# Sheet1.net
KiCad netlist of a schematic drawn in Altium Designer
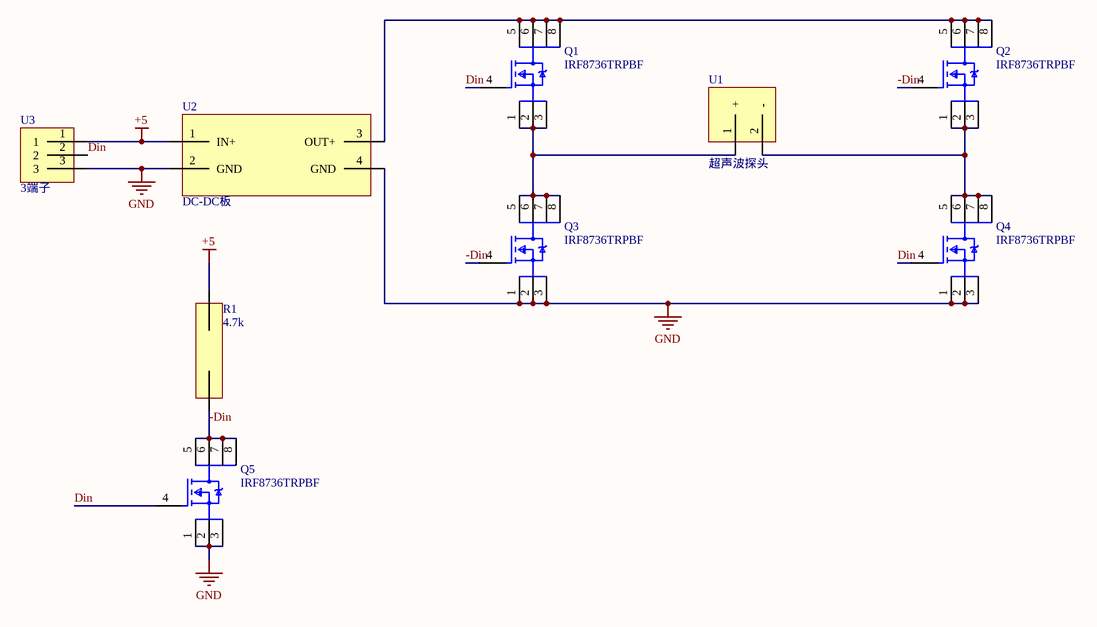
[diagram p0: Sheet1.SchDoc]

(export (version "E")
  (design (tool "Eeschema 10.0.6"))
  (components
    (comp (ref "Q1")
      (value "IRF8736TRPBF")
      (footprint "FP-PG-DSO-8-MFG")
      (description "MOSFET N-CH 30V 18A 8-SOIC")
      (fields
        (field (name "MANUFACTURER") "Infineon")
        (field (name "OCTOPART") "https://octopart.com/irf8736trpbf-infineon-65873731")
      )
      (libsource (lib "Altium Content Vault") (part "6c4379695d6b9ddabb25581bf066c8b"))
    )
    (comp (ref "Q2")
      (value "IRF8736TRPBF")
      (footprint "FP-PG-DSO-8-MFG")
      (description "MOSFET N-CH 30V 18A 8-SOIC")
      (fields
        (field (name "MANUFACTURER") "Infineon")
        (field (name "OCTOPART") "https://octopart.com/irf8736trpbf-infineon-65873731")
      )
      (libsource (lib "Altium Content Vault") (part "6c4379695d6b9ddabb25581bf066c8b"))
    )
    (comp (ref "Q3")
      (value "IRF8736TRPBF")
      (footprint "FP-PG-DSO-8-MFG")
      (description "MOSFET N-CH 30V 18A 8-SOIC")
      (fields
        (field (name "MANUFACTURER") "Infineon")
        (field (name "OCTOPART") "https://octopart.com/irf8736trpbf-infineon-65873731")
      )
      (libsource (lib "Altium Content Vault") (part "6c4379695d6b9ddabb25581bf066c8b"))
    )
    (comp (ref "Q4")
      (value "IRF8736TRPBF")
      (footprint "FP-PG-DSO-8-MFG")
      (description "MOSFET N-CH 30V 18A 8-SOIC")
      (fields
        (field (name "MANUFACTURER") "Infineon")
        (field (name "OCTOPART") "https://octopart.com/irf8736trpbf-infineon-65873731")
      )
      (libsource (lib "Altium Content Vault") (part "6c4379695d6b9ddabb25581bf066c8b"))
    )
    (comp (ref "Q5")
      (value "IRF8736TRPBF")
      (footprint "FP-PG-DSO-8-MFG")
      (description "MOSFET N-CH 30V 18A 8-SOIC")
      (fields
        (field (name "MANUFACTURER") "Infineon")
        (field (name "OCTOPART") "https://octopart.com/irf8736trpbf-infineon-65873731")
      )
      (libsource (lib "Altium Content Vault") (part "6c4379695d6b9ddabb25581bf066c8b"))
    )
    (comp (ref "R1") (value "4.7k") (footprint "0603") (libsource (lib "Schlib1") (part "0603")))
    (comp (ref "U1") (value "超声波探头") (footprint "超声波探头") (libsource (lib "Schlib1") (part "超声波探头")))
    (comp (ref "U2") (value "DC-DC板") (footprint "DC-DC板") (libsource (lib "Schlib1") (part "DC-DC板")))
    (comp (ref "U3") (value "3端子") (footprint "HDR2.54-LI-3P") (libsource (lib "Schlib1") (part "3端子")))
  )
  (nets
    (net (code "1") (name "+5") (class "Default")
      (node (ref "R1") (pin "2") (pinfunction "2_2") (pintype "passive"))
      (node (ref "U2") (pin "1") (pinfunction "IN+_1") (pintype "passive"))
      (node (ref "U3") (pin "1") (pinfunction "1_1") (pintype "passive"))
    )
    (net (code "2") (name "/-Din") (class "Default")
      (node (ref "Q2") (pin "4") (pinfunction "G_4") (pintype "passive"))
      (node (ref "Q3") (pin "4") (pinfunction "G_4") (pintype "passive"))
      (node (ref "Q5") (pin "5") (pinfunction "D_5") (pintype "passive"))
      (node (ref "Q5") (pin "6") (pinfunction "D_6") (pintype "passive"))
      (node (ref "Q5") (pin "7") (pinfunction "D_7") (pintype "passive"))
      (node (ref "Q5") (pin "8") (pinfunction "D_8") (pintype "passive"))
      (node (ref "R1") (pin "1") (pinfunction "1_1") (pintype "passive"))
    )
    (net (code "3") (name "/Din") (class "Default")
      (node (ref "Q1") (pin "4") (pinfunction "G_4") (pintype "passive"))
      (node (ref "Q4") (pin "4") (pinfunction "G_4") (pintype "passive"))
      (node (ref "Q5") (pin "4") (pinfunction "G_4") (pintype "passive"))
      (node (ref "U3") (pin "2") (pinfunction "2_2") (pintype "passive"))
    )
    (net (code "4") (name "GND") (class "Default")
      (node (ref "Q3") (pin "1") (pinfunction "S_1") (pintype "passive"))
      (node (ref "Q3") (pin "2") (pinfunction "S_2") (pintype "passive"))
      (node (ref "Q3") (pin "3") (pinfunction "S_3") (pintype "passive"))
      (node (ref "Q4") (pin "1") (pinfunction "S_1") (pintype "passive"))
      (node (ref "Q4") (pin "2") (pinfunction "S_2") (pintype "passive"))
      (node (ref "Q4") (pin "3") (pinfunction "S_3") (pintype "passive"))
      (node (ref "Q5") (pin "1") (pinfunction "S_1") (pintype "passive"))
      (node (ref "Q5") (pin "2") (pinfunction "S_2") (pintype "passive"))
      (node (ref "Q5") (pin "3") (pinfunction "S_3") (pintype "passive"))
      (node (ref "U2") (pin "2") (pinfunction "GND_2") (pintype "passive"))
      (node (ref "U2") (pin "4") (pinfunction "GND_4") (pintype "passive"))
      (node (ref "U3") (pin "3") (pinfunction "3_3") (pintype "passive"))
    )
    (net (code "5") (name "Net-(U1-+)") (class "Default")
      (node (ref "Q1") (pin "1") (pinfunction "S_1") (pintype "passive"))
      (node (ref "Q1") (pin "2") (pinfunction "S_2") (pintype "passive"))
      (node (ref "Q1") (pin "3") (pinfunction "S_3") (pintype "passive"))
      (node (ref "Q3") (pin "5") (pinfunction "D_5") (pintype "passive"))
      (node (ref "Q3") (pin "6") (pinfunction "D_6") (pintype "passive"))
      (node (ref "Q3") (pin "7") (pinfunction "D_7") (pintype "passive"))
      (node (ref "Q3") (pin "8") (pinfunction "D_8") (pintype "passive"))
      (node (ref "U1") (pin "1") (pinfunction "+_1") (pintype "passive"))
    )
    (net (code "6") (name "Net-(U1--)") (class "Default")
      (node (ref "Q2") (pin "1") (pinfunction "S_1") (pintype "passive"))
      (node (ref "Q2") (pin "2") (pinfunction "S_2") (pintype "passive"))
      (node (ref "Q2") (pin "3") (pinfunction "S_3") (pintype "passive"))
      (node (ref "Q4") (pin "5") (pinfunction "D_5") (pintype "passive"))
      (node (ref "Q4") (pin "6") (pinfunction "D_6") (pintype "passive"))
      (node (ref "Q4") (pin "7") (pinfunction "D_7") (pintype "passive"))
      (node (ref "Q4") (pin "8") (pinfunction "D_8") (pintype "passive"))
      (node (ref "U1") (pin "2") (pinfunction "-_2") (pintype "passive"))
    )
    (net (code "7") (name "Net-(U2-OUT+)") (class "Default")
      (node (ref "Q1") (pin "5") (pinfunction "D_5") (pintype "passive"))
      (node (ref "Q1") (pin "6") (pinfunction "D_6") (pintype "passive"))
      (node (ref "Q1") (pin "7") (pinfunction "D_7") (pintype "passive"))
      (node (ref "Q1") (pin "8") (pinfunction "D_8") (pintype "passive"))
      (node (ref "Q2") (pin "5") (pinfunction "D_5") (pintype "passive"))
      (node (ref "Q2") (pin "6") (pinfunction "D_6") (pintype "passive"))
      (node (ref "Q2") (pin "7") (pinfunction "D_7") (pintype "passive"))
      (node (ref "Q2") (pin "8") (pinfunction "D_8") (pintype "passive"))
      (node (ref "U2") (pin "3") (pinfunction "OUT+_3") (pintype "passive"))
    )
  )
)
